# MicroController.net
KiCad netlist of a schematic drawn in Altium Designer
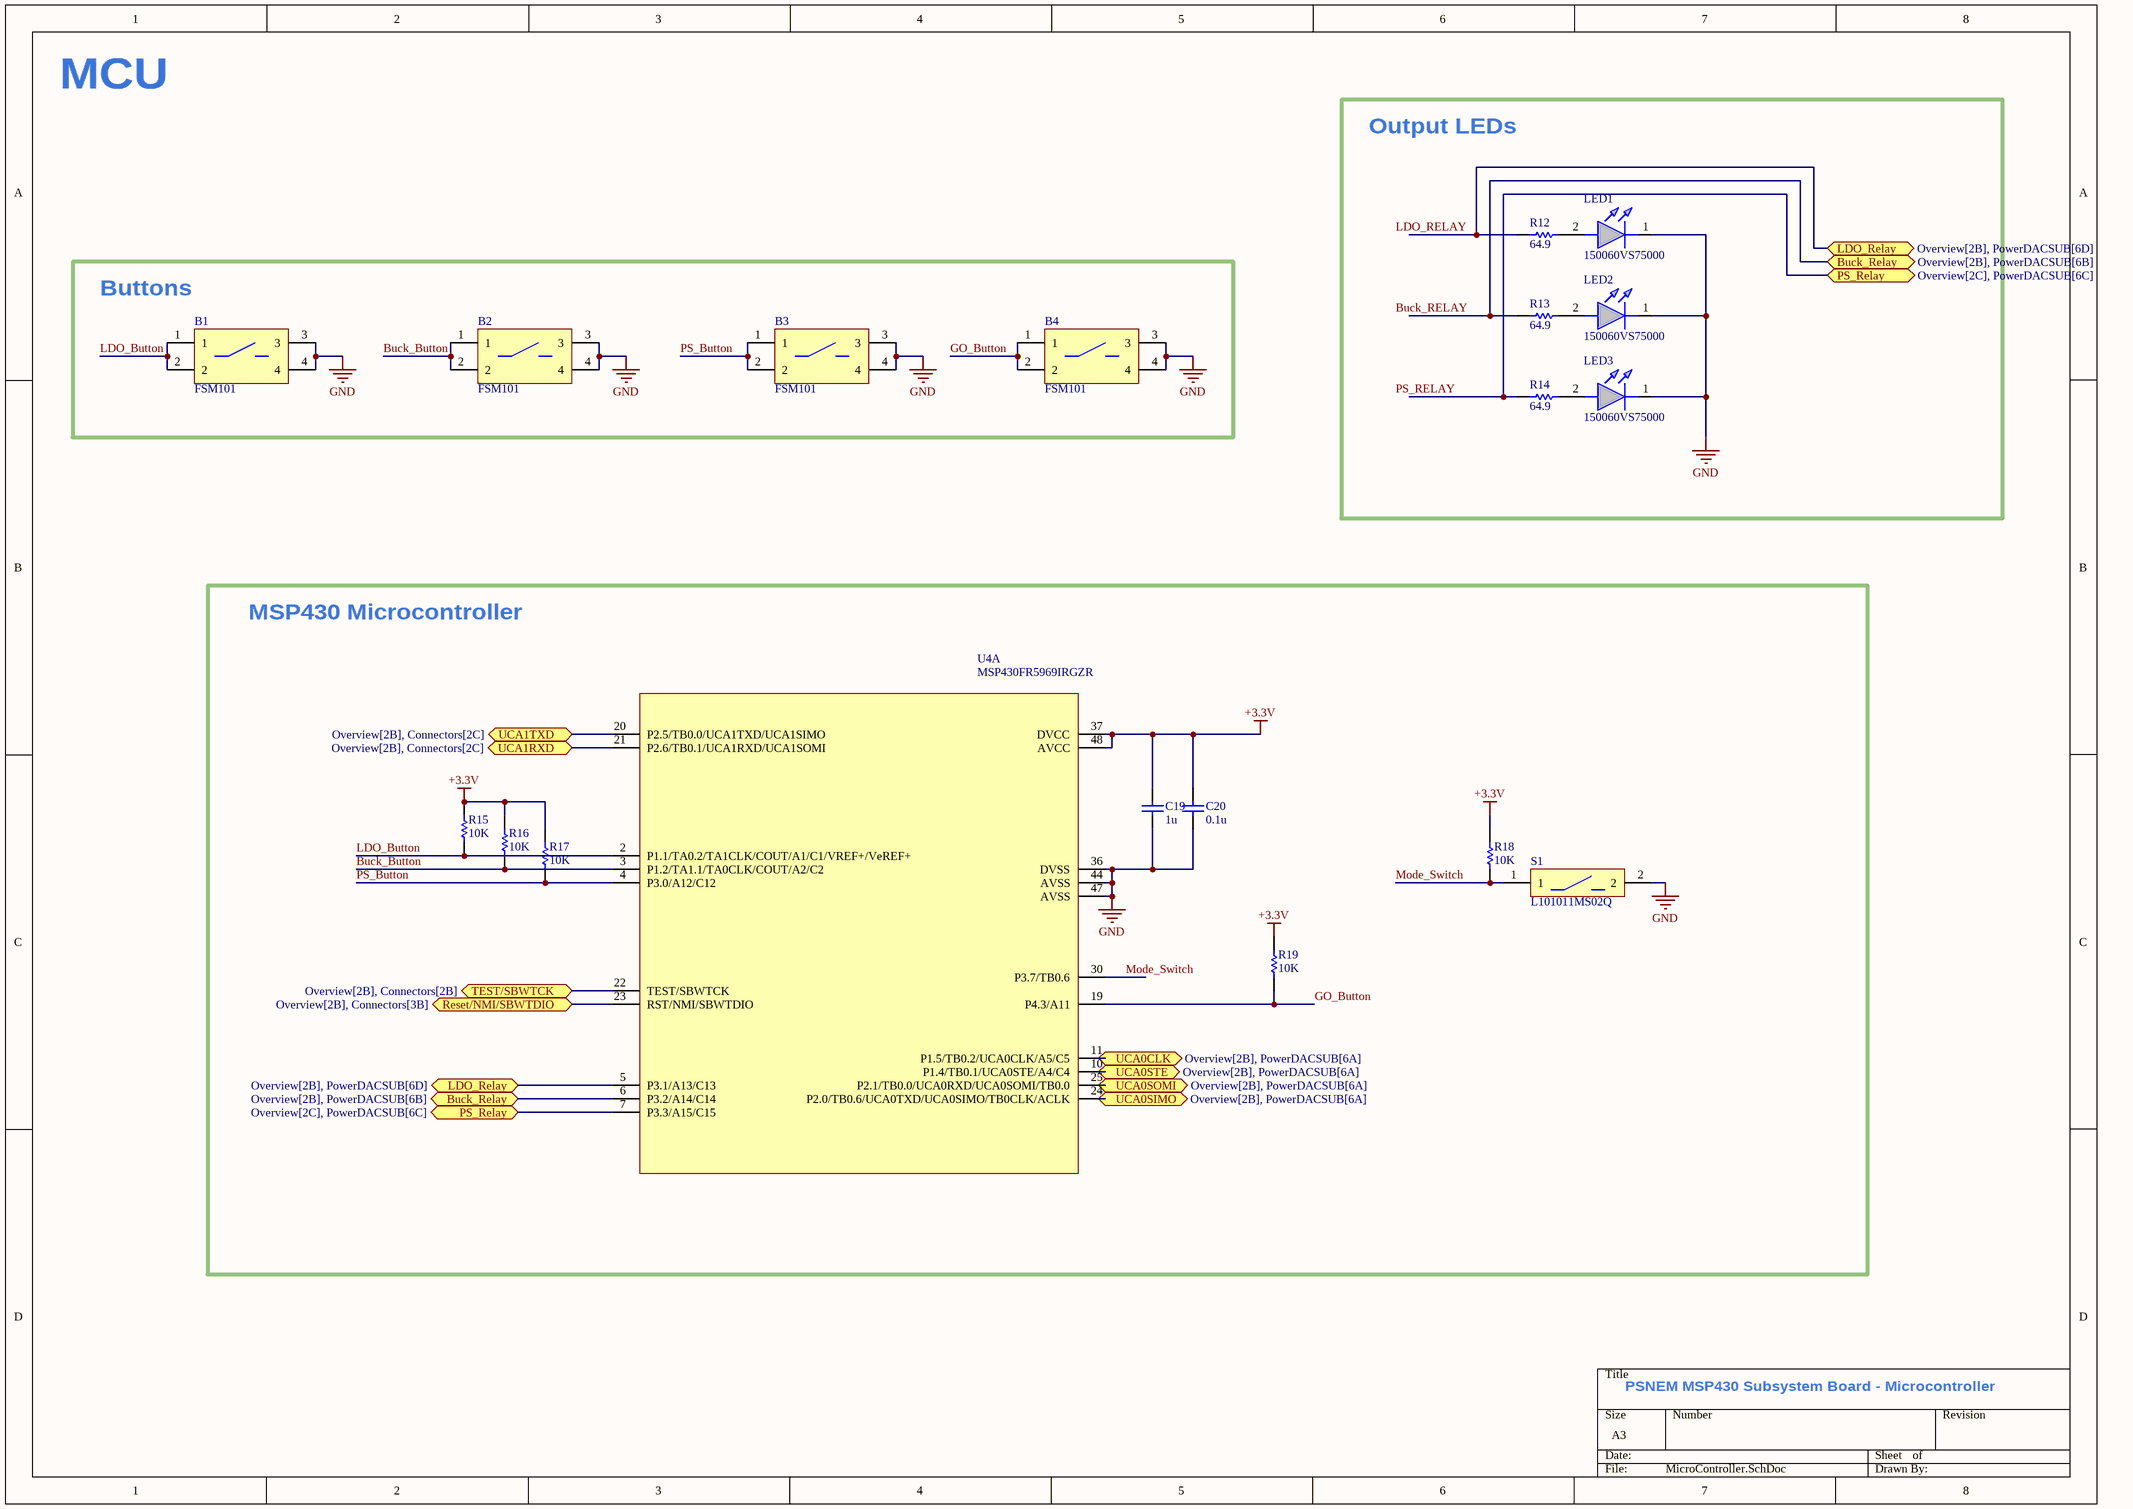
[diagram p0: MicroController.SchDoc]

(export (version "E")
  (design (tool "Eeschema 10.0.6"))
  (components
    (comp (ref "B1")
      (value "FSM101")
      (footprint "FSM101")
      (description "Tactile Switch SPST-NO Top Actuated Through Hole")
      (libsource (lib "Schlib1") (part "FSM101"))
    )
    (comp (ref "B2")
      (value "FSM101")
      (footprint "FSM101")
      (description "Tactile Switch SPST-NO Top Actuated Through Hole")
      (libsource (lib "Schlib1") (part "FSM101"))
    )
    (comp (ref "B3")
      (value "FSM101")
      (footprint "FSM101")
      (description "Tactile Switch SPST-NO Top Actuated Through Hole")
      (libsource (lib "Schlib1") (part "FSM101"))
    )
    (comp (ref "B4")
      (value "FSM101")
      (footprint "FSM101")
      (description "Tactile Switch SPST-NO Top Actuated Through Hole")
      (libsource (lib "Schlib1") (part "FSM101"))
    )
    (comp (ref "C19")
      (value "1u")
      (footprint "0805 Cap")
      (description "1 µF ±10% 16V Ceramic Capacitor X7R 0805 (2012 Metric)")
      (libsource (lib "Schlib1") (part "CC0805KKX7R7BB105"))
    )
    (comp (ref "C20")
      (value "0.1u")
      (footprint "0805 Cap")
      (description "0.1 µF ±10% 50V Ceramic Capacitor X7R 0805 (2012 Metric)")
      (libsource (lib "Schlib1") (part "CC0805KRX7R9BB104"))
    )
    (comp (ref "LED1")
      (value "150060VS75000")
      (footprint "150060VS75000")
      (description "LED GREEN CLEAR 0603 SMD")
      (libsource (lib "Schlib1") (part "150060VS75000"))
    )
    (comp (ref "LED2")
      (value "150060VS75000")
      (footprint "150060VS75000")
      (description "LED GREEN CLEAR 0603 SMD")
      (libsource (lib "Schlib1") (part "150060VS75000"))
    )
    (comp (ref "LED3")
      (value "150060VS75000")
      (footprint "150060VS75000")
      (description "LED GREEN CLEAR 0603 SMD")
      (libsource (lib "Schlib1") (part "150060VS75000"))
    )
    (comp (ref "R12")
      (value "64.9")
      (footprint "RESC1608X06N")
      (description "Thin Film Resistors - SMD 0603 64.9ohm 0.1% 25ppm")
      (libsource (lib "Schlib1") (part "ERA-3AEB64R9V"))
    )
    (comp (ref "R13")
      (value "64.9")
      (footprint "RESC1608X06N")
      (description "Thin Film Resistors - SMD 0603 64.9ohm 0.1% 25ppm")
      (libsource (lib "Schlib1") (part "ERA-3AEB64R9V"))
    )
    (comp (ref "R14")
      (value "64.9")
      (footprint "RESC1608X06N")
      (description "Thin Film Resistors - SMD 0603 64.9ohm 0.1% 25ppm")
      (libsource (lib "Schlib1") (part "ERA-3AEB64R9V"))
    )
    (comp (ref "R15")
      (value "10K")
      (footprint "RESC1608X06N")
      (description "RES SMD 10K OHM 1% 1/3W 0603")
      (libsource (lib "Schlib1") (part "CRCW060310K0FKEAHP"))
    )
    (comp (ref "R16")
      (value "10K")
      (footprint "RESC1608X06N")
      (description "RES SMD 10K OHM 1% 1/3W 0603")
      (libsource (lib "Schlib1") (part "CRCW060310K0FKEAHP"))
    )
    (comp (ref "R17")
      (value "10K")
      (footprint "RESC1608X06N")
      (description "RES SMD 10K OHM 1% 1/3W 0603")
      (libsource (lib "Schlib1") (part "CRCW060310K0FKEAHP"))
    )
    (comp (ref "R18")
      (value "10K")
      (footprint "RESC1608X06N")
      (description "RES SMD 10K OHM 1% 1/3W 0603")
      (libsource (lib "Schlib1") (part "CRCW060310K0FKEAHP"))
    )
    (comp (ref "R19")
      (value "10K")
      (footprint "RESC1608X06N")
      (description "RES SMD 10K OHM 1% 1/3W 0603")
      (libsource (lib "Schlib1") (part "CRCW060310K0FKEAHP"))
    )
    (comp (ref "S1")
      (value "L101011MS02Q")
      (footprint "L101011MS02Q")
      (description "SWITCH SLIDE SPST 4A 125V")
      (libsource (lib "Schlib1") (part "L101011MS02Q"))
    )
    (comp (ref "U4")
      (value "MSP430FR5969IRGZR")
      (footprint "MSP430FR5969IRGZR")
      (description "MSP430 CPUXV2 MSP430™ FRAM Microcontroller IC 16-Bit 16MHz 64KB (64K x 8) FRAM 48-VQFN (7x7)")
      (libsource (lib "Schlib1") (part "MSP430FR5969IRGZR"))
    )
  )
  (nets
    (net (code "1") (name "+3.3V") (class "Default")
      (node (ref "C19") (pin "2") (pinfunction "2_2") (pintype "passive"))
      (node (ref "C20") (pin "2") (pinfunction "2_2") (pintype "passive"))
      (node (ref "R15") (pin "2") (pinfunction "2_2") (pintype "passive"))
      (node (ref "R16") (pin "2") (pinfunction "2_2") (pintype "passive"))
      (node (ref "R17") (pin "2") (pinfunction "2_2") (pintype "passive"))
      (node (ref "R18") (pin "2") (pinfunction "2_2") (pintype "passive"))
      (node (ref "R19") (pin "2") (pinfunction "2_2") (pintype "passive"))
      (node (ref "U4") (pin "37") (pinfunction "DVCC_37") (pintype "passive"))
      (node (ref "U4") (pin "48") (pinfunction "AVCC_48") (pintype "passive"))
    )
    (net (code "2") (name "/Buck_Button") (class "Default")
      (node (ref "B2") (pin "1") (pinfunction "1_1") (pintype "passive"))
      (node (ref "B2") (pin "2") (pinfunction "2_2") (pintype "passive"))
      (node (ref "R16") (pin "1") (pinfunction "1_1") (pintype "passive"))
      (node (ref "U4") (pin "3") (pinfunction "P1.2/TA1.1/TA0CLK/COUT/A2/C2_3") (pintype "passive"))
    )
    (net (code "4") (name "/Buck_Relay") (class "Default")
      (node (ref "R13") (pin "1") (pinfunction "1_1") (pintype "passive"))
      (node (ref "U4") (pin "6") (pinfunction "P3.2/A14/C14_6") (pintype "passive"))
    )
    (net (code "5") (name "/GO_Button") (class "Default")
      (node (ref "B4") (pin "1") (pinfunction "1_1") (pintype "passive"))
      (node (ref "B4") (pin "2") (pinfunction "2_2") (pintype "passive"))
      (node (ref "R19") (pin "1") (pinfunction "1_1") (pintype "passive"))
      (node (ref "U4") (pin "19") (pinfunction "P4.3/A11_19") (pintype "passive"))
    )
    (net (code "6") (name "/LDO_Button") (class "Default")
      (node (ref "B1") (pin "1") (pinfunction "1_1") (pintype "passive"))
      (node (ref "B1") (pin "2") (pinfunction "2_2") (pintype "passive"))
      (node (ref "R15") (pin "1") (pinfunction "1_1") (pintype "passive"))
      (node (ref "U4") (pin "2") (pinfunction "P1.1/TA0.2/TA1CLK/COUT/A1/C1/VREF+/VeREF+_2") (pintype "passive"))
    )
    (net (code "8") (name "/LDO_Relay") (class "Default")
      (node (ref "R12") (pin "1") (pinfunction "1_1") (pintype "passive"))
      (node (ref "U4") (pin "5") (pinfunction "P3.1/A13/C13_5") (pintype "passive"))
    )
    (net (code "9") (name "/Mode_Switch") (class "Default")
      (node (ref "R18") (pin "1") (pinfunction "1_1") (pintype "passive"))
      (node (ref "S1") (pin "1") (pinfunction "1_1") (pintype "passive"))
      (node (ref "U4") (pin "30") (pinfunction "P3.7/TB0.6_30") (pintype "passive"))
    )
    (net (code "10") (name "/PS_Button") (class "Default")
      (node (ref "B3") (pin "1") (pinfunction "1_1") (pintype "passive"))
      (node (ref "B3") (pin "2") (pinfunction "2_2") (pintype "passive"))
      (node (ref "R17") (pin "1") (pinfunction "1_1") (pintype "passive"))
      (node (ref "U4") (pin "4") (pinfunction "P3.0/A12/C12_4") (pintype "passive"))
    )
    (net (code "12") (name "/PS_Relay") (class "Default")
      (node (ref "R14") (pin "1") (pinfunction "1_1") (pintype "passive"))
      (node (ref "U4") (pin "7") (pinfunction "P3.3/A15/C15_7") (pintype "passive"))
    )
    (net (code "13") (name "/Reset{slash}NMI{slash}SBWTDIO") (class "Default")
      (node (ref "U4") (pin "23") (pinfunction "RST/NMI/SBWTDIO_23") (pintype "passive"))
    )
    (net (code "14") (name "/TEST{slash}SBWTCK") (class "Default")
      (node (ref "U4") (pin "22") (pinfunction "TEST/SBWTCK_22") (pintype "passive"))
    )
    (net (code "15") (name "/UCA0CLK") (class "Default")
      (node (ref "U4") (pin "11") (pinfunction "P1.5/TB0.2/UCA0CLK/A5/C5_11") (pintype "passive"))
    )
    (net (code "16") (name "/UCA0SIMO") (class "Default")
      (node (ref "U4") (pin "24") (pinfunction "P2.0/TB0.6/UCA0TXD/UCA0SIMO/TB0CLK/ACLK_24") (pintype "passive"))
    )
    (net (code "17") (name "/UCA0SOMI") (class "Default")
      (node (ref "U4") (pin "25") (pinfunction "P2.1/TB0.0/UCA0RXD/UCA0SOMI/TB0.0_25") (pintype "passive"))
    )
    (net (code "18") (name "/UCA0STE") (class "Default")
      (node (ref "U4") (pin "10") (pinfunction "P1.4/TB0.1/UCA0STE/A4/C4_10") (pintype "passive"))
    )
    (net (code "19") (name "/UCA1RXD") (class "Default")
      (node (ref "U4") (pin "21") (pinfunction "P2.6/TB0.1/UCA1RXD/UCA1SOMI_21") (pintype "passive"))
    )
    (net (code "20") (name "/UCA1TXD") (class "Default")
      (node (ref "U4") (pin "20") (pinfunction "P2.5/TB0.0/UCA1TXD/UCA1SIMO_20") (pintype "passive"))
    )
    (net (code "21") (name "GND") (class "Default")
      (node (ref "B1") (pin "3") (pinfunction "3_3") (pintype "passive"))
      (node (ref "B1") (pin "4") (pinfunction "4_4") (pintype "passive"))
      (node (ref "B2") (pin "3") (pinfunction "3_3") (pintype "passive"))
      (node (ref "B2") (pin "4") (pinfunction "4_4") (pintype "passive"))
      (node (ref "B3") (pin "3") (pinfunction "3_3") (pintype "passive"))
      (node (ref "B3") (pin "4") (pinfunction "4_4") (pintype "passive"))
      (node (ref "B4") (pin "3") (pinfunction "3_3") (pintype "passive"))
      (node (ref "B4") (pin "4") (pinfunction "4_4") (pintype "passive"))
      (node (ref "C19") (pin "1") (pinfunction "1_1") (pintype "passive"))
      (node (ref "C20") (pin "1") (pinfunction "1_1") (pintype "passive"))
      (node (ref "LED1") (pin "1") (pinfunction "K_1") (pintype "passive"))
      (node (ref "LED2") (pin "1") (pinfunction "K_1") (pintype "passive"))
      (node (ref "LED3") (pin "1") (pinfunction "K_1") (pintype "passive"))
      (node (ref "S1") (pin "2") (pinfunction "2_2") (pintype "passive"))
      (node (ref "U4") (pin "36") (pinfunction "DVSS_36") (pintype "passive"))
      (node (ref "U4") (pin "44") (pinfunction "AVSS_44") (pintype "passive"))
      (node (ref "U4") (pin "47") (pinfunction "AVSS_47") (pintype "passive"))
    )
    (net (code "22") (name "Net-(LED1-A)") (class "Default")
      (node (ref "LED1") (pin "2") (pinfunction "A_2") (pintype "passive"))
      (node (ref "R12") (pin "2") (pinfunction "2_2") (pintype "passive"))
    )
    (net (code "23") (name "Net-(LED2-A)") (class "Default")
      (node (ref "LED2") (pin "2") (pinfunction "A_2") (pintype "passive"))
      (node (ref "R13") (pin "2") (pinfunction "2_2") (pintype "passive"))
    )
    (net (code "24") (name "Net-(LED3-A)") (class "Default")
      (node (ref "LED3") (pin "2") (pinfunction "A_2") (pintype "passive"))
      (node (ref "R14") (pin "2") (pinfunction "2_2") (pintype "passive"))
    )
  )
)
